# Light-Adapter_SMD.net
KiCad netlist of a schematic drawn in EAGLE
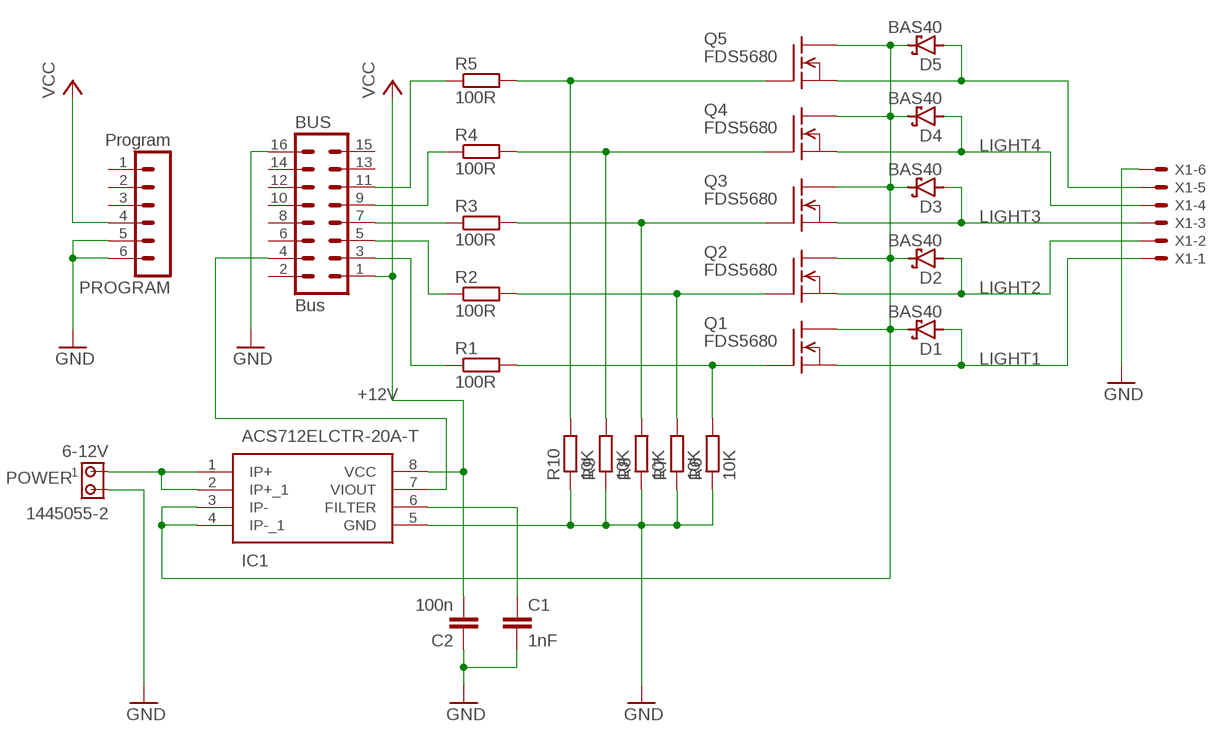
[diagram p0: schematic, sheet 1]

(export (version "E")
  (design (tool "Eeschema 10.0.6"))
  (components
    (comp (ref "6-12V")
      (value "1445055-2")
      (footprint "eagle-import:1445055-2")
      (libsource (lib "eagle-import") (part "1445055-2"))
    )
    (comp (ref "BUS")
      (value "Bus")
      (footprint "eagle-import:MA08-2")
      (libsource (lib "eagle-import") (part "MA08-2"))
    )
    (comp (ref "C1")
      (value "1nF")
      (footprint "eagle-import:C0402")
      (libsource (lib "eagle-import") (part "C-EUC0402"))
    )
    (comp (ref "C2")
      (value "100n")
      (footprint "eagle-import:C0402")
      (libsource (lib "eagle-import") (part "C-EUC0402"))
    )
    (comp (ref "D1")
      (value "BAS40")
      (footprint "eagle-import:SOT23")
      (libsource (lib "eagle-import") (part "BAS40"))
    )
    (comp (ref "D2")
      (value "BAS40")
      (footprint "eagle-import:SOT23")
      (libsource (lib "eagle-import") (part "BAS40"))
    )
    (comp (ref "D3")
      (value "BAS40")
      (footprint "eagle-import:SOT23")
      (libsource (lib "eagle-import") (part "BAS40"))
    )
    (comp (ref "D4")
      (value "BAS40")
      (footprint "eagle-import:SOT23")
      (libsource (lib "eagle-import") (part "BAS40"))
    )
    (comp (ref "D5")
      (value "BAS40")
      (footprint "eagle-import:SOT23")
      (libsource (lib "eagle-import") (part "BAS40"))
    )
    (comp (ref "IC1")
      (value "ACS712ELCTR-20A-T")
      (footprint "eagle-import:SOIC127P600X175-8N")
      (fields (field (name "RS_PART_NUMBER") "6807135P"))
      (libsource (lib "eagle-import") (part "ACS712ELCTR-20A-T"))
    )
    (comp (ref "PROGRAM")
      (value "Program")
      (footprint "eagle-import:MA06-1")
      (libsource (lib "eagle-import") (part "MA06-1"))
    )
    (comp (ref "Q1")
      (value "FDS5680")
      (footprint "eagle-import:SO-8")
      (libsource (lib "eagle-import") (part "FDS5680"))
    )
    (comp (ref "Q2")
      (value "FDS5680")
      (footprint "eagle-import:SO-8")
      (libsource (lib "eagle-import") (part "FDS5680"))
    )
    (comp (ref "Q3")
      (value "FDS5680")
      (footprint "eagle-import:SO-8")
      (libsource (lib "eagle-import") (part "FDS5680"))
    )
    (comp (ref "Q4")
      (value "FDS5680")
      (footprint "eagle-import:SO-8")
      (libsource (lib "eagle-import") (part "FDS5680"))
    )
    (comp (ref "Q5")
      (value "FDS5680")
      (footprint "eagle-import:SO-8")
      (libsource (lib "eagle-import") (part "FDS5680"))
    )
    (comp (ref "R1")
      (value "100R")
      (footprint "eagle-import:R0402")
      (libsource (lib "eagle-import") (part "R-EU_R0402"))
    )
    (comp (ref "R2")
      (value "100R")
      (footprint "eagle-import:R0402")
      (libsource (lib "eagle-import") (part "R-EU_R0402"))
    )
    (comp (ref "R3")
      (value "100R")
      (footprint "eagle-import:R0402")
      (libsource (lib "eagle-import") (part "R-EU_R0402"))
    )
    (comp (ref "R4")
      (value "100R")
      (footprint "eagle-import:R0402")
      (libsource (lib "eagle-import") (part "R-EU_R0402"))
    )
    (comp (ref "R5")
      (value "100R")
      (footprint "eagle-import:R0402")
      (libsource (lib "eagle-import") (part "R-EU_R0402"))
    )
    (comp (ref "R6")
      (value "10K")
      (footprint "eagle-import:R0402")
      (libsource (lib "eagle-import") (part "R-EU_R0402"))
    )
    (comp (ref "R7")
      (value "10K")
      (footprint "eagle-import:R0402")
      (libsource (lib "eagle-import") (part "R-EU_R0402"))
    )
    (comp (ref "R8")
      (value "10K")
      (footprint "eagle-import:R0402")
      (libsource (lib "eagle-import") (part "R-EU_R0402"))
    )
    (comp (ref "R9")
      (value "10K")
      (footprint "eagle-import:R0402")
      (libsource (lib "eagle-import") (part "R-EU_R0402"))
    )
    (comp (ref "R10")
      (value "10K")
      (footprint "eagle-import:R0402")
      (libsource (lib "eagle-import") (part "R-EU_R0402"))
    )
    (comp (ref "X1")
      (value "22-23-2061")
      (footprint "eagle-import:22-23-2061")
      (fields (field (name "MF") "MOLEX"))
      (libsource (lib "eagle-import") (part "22-23-2061"))
    )
  )
  (nets
    (net (code "1") (name "/+12V") (class "Default")
      (node (ref "D1") (pin "3") (pinfunction "C_3") (pintype "passive"))
      (node (ref "D2") (pin "3") (pinfunction "C_3") (pintype "passive"))
      (node (ref "D3") (pin "3") (pinfunction "C_3") (pintype "passive"))
      (node (ref "D4") (pin "3") (pinfunction "C_3") (pintype "passive"))
      (node (ref "D5") (pin "3") (pinfunction "C_3") (pintype "passive"))
      (node (ref "IC1") (pin "3") (pinfunction "IP-_3") (pintype "bidirectional"))
      (node (ref "IC1") (pin "4") (pinfunction "IP-_1_4") (pintype "bidirectional"))
      (node (ref "Q1") (pin "5") (pinfunction "D_5") (pintype "passive"))
      (node (ref "Q1") (pin "6") (pinfunction "D_6") (pintype "passive"))
      (node (ref "Q1") (pin "7") (pinfunction "D_7") (pintype "passive"))
      (node (ref "Q1") (pin "8") (pinfunction "D_8") (pintype "passive"))
      (node (ref "Q2") (pin "5") (pinfunction "D_5") (pintype "passive"))
      (node (ref "Q2") (pin "6") (pinfunction "D_6") (pintype "passive"))
      (node (ref "Q2") (pin "7") (pinfunction "D_7") (pintype "passive"))
      (node (ref "Q2") (pin "8") (pinfunction "D_8") (pintype "passive"))
      (node (ref "Q3") (pin "5") (pinfunction "D_5") (pintype "passive"))
      (node (ref "Q3") (pin "6") (pinfunction "D_6") (pintype "passive"))
      (node (ref "Q3") (pin "7") (pinfunction "D_7") (pintype "passive"))
      (node (ref "Q3") (pin "8") (pinfunction "D_8") (pintype "passive"))
      (node (ref "Q4") (pin "5") (pinfunction "D_5") (pintype "passive"))
      (node (ref "Q4") (pin "6") (pinfunction "D_6") (pintype "passive"))
      (node (ref "Q4") (pin "7") (pinfunction "D_7") (pintype "passive"))
      (node (ref "Q4") (pin "8") (pinfunction "D_8") (pintype "passive"))
      (node (ref "Q5") (pin "5") (pinfunction "D_5") (pintype "passive"))
      (node (ref "Q5") (pin "6") (pinfunction "D_6") (pintype "passive"))
      (node (ref "Q5") (pin "7") (pinfunction "D_7") (pintype "passive"))
      (node (ref "Q5") (pin "8") (pinfunction "D_8") (pintype "passive"))
    )
    (net (code "2") (name "/LIGHT1") (class "Default")
      (node (ref "D1") (pin "1") (pinfunction "A_1") (pintype "passive"))
      (node (ref "Q1") (pin "1") (pinfunction "S_1") (pintype "passive"))
      (node (ref "Q1") (pin "2") (pinfunction "S_2") (pintype "passive"))
      (node (ref "Q1") (pin "3") (pinfunction "S_3") (pintype "passive"))
      (node (ref "X1") (pin "1") (pinfunction "S_1") (pintype "passive"))
    )
    (net (code "3") (name "/LIGHT2") (class "Default")
      (node (ref "D2") (pin "1") (pinfunction "A_1") (pintype "passive"))
      (node (ref "Q2") (pin "1") (pinfunction "S_1") (pintype "passive"))
      (node (ref "Q2") (pin "2") (pinfunction "S_2") (pintype "passive"))
      (node (ref "Q2") (pin "3") (pinfunction "S_3") (pintype "passive"))
      (node (ref "X1") (pin "2") (pinfunction "S_2") (pintype "passive"))
    )
    (net (code "4") (name "/LIGHT3") (class "Default")
      (node (ref "D3") (pin "1") (pinfunction "A_1") (pintype "passive"))
      (node (ref "Q3") (pin "1") (pinfunction "S_1") (pintype "passive"))
      (node (ref "Q3") (pin "2") (pinfunction "S_2") (pintype "passive"))
      (node (ref "Q3") (pin "3") (pinfunction "S_3") (pintype "passive"))
      (node (ref "X1") (pin "3") (pinfunction "S_3") (pintype "passive"))
    )
    (net (code "5") (name "/LIGHT4") (class "Default")
      (node (ref "D4") (pin "1") (pinfunction "A_1") (pintype "passive"))
      (node (ref "Q4") (pin "1") (pinfunction "S_1") (pintype "passive"))
      (node (ref "Q4") (pin "2") (pinfunction "S_2") (pintype "passive"))
      (node (ref "Q4") (pin "3") (pinfunction "S_3") (pintype "passive"))
      (node (ref "X1") (pin "4") (pinfunction "S_4") (pintype "passive"))
    )
    (net (code "6") (name "/POWER") (class "Default")
      (node (ref "6-12V") (pin "1") (pinfunction "1_1") (pintype "passive"))
      (node (ref "IC1") (pin "1") (pinfunction "IP+_1") (pintype "bidirectional"))
      (node (ref "IC1") (pin "2") (pinfunction "IP+_1_2") (pintype "bidirectional"))
    )
    (net (code "7") (name "GND") (class "Default")
      (node (ref "6-12V") (pin "2") (pinfunction "2_2") (pintype "passive"))
      (node (ref "BUS") (pin "16") (pinfunction "16_16") (pintype "passive"))
      (node (ref "C1") (pin "2") (pinfunction "2_2") (pintype "passive"))
      (node (ref "C2") (pin "1") (pinfunction "1_1") (pintype "passive"))
      (node (ref "IC1") (pin "5") (pinfunction "GND_5") (pintype "power_in"))
      (node (ref "PROGRAM") (pin "5") (pinfunction "5_5") (pintype "passive"))
      (node (ref "PROGRAM") (pin "6") (pinfunction "6_6") (pintype "passive"))
      (node (ref "R10") (pin "1") (pinfunction "1_1") (pintype "passive"))
      (node (ref "R6") (pin "1") (pinfunction "1_1") (pintype "passive"))
      (node (ref "R7") (pin "1") (pinfunction "1_1") (pintype "passive"))
      (node (ref "R8") (pin "1") (pinfunction "1_1") (pintype "passive"))
      (node (ref "R9") (pin "1") (pinfunction "1_1") (pintype "passive"))
      (node (ref "X1") (pin "6") (pinfunction "S_6") (pintype "passive"))
    )
    (net (code "8") (name "Net-(BUS-Pad3)") (class "Default")
      (node (ref "BUS") (pin "3") (pinfunction "3_3") (pintype "passive"))
      (node (ref "R1") (pin "1") (pinfunction "1_1") (pintype "passive"))
    )
    (net (code "9") (name "Net-(BUS-Pad5)") (class "Default")
      (node (ref "BUS") (pin "5") (pinfunction "5_5") (pintype "passive"))
      (node (ref "R2") (pin "1") (pinfunction "1_1") (pintype "passive"))
    )
    (net (code "10") (name "Net-(BUS-Pad7)") (class "Default")
      (node (ref "BUS") (pin "7") (pinfunction "7_7") (pintype "passive"))
      (node (ref "R3") (pin "1") (pinfunction "1_1") (pintype "passive"))
    )
    (net (code "11") (name "Net-(BUS-Pad9)") (class "Default")
      (node (ref "BUS") (pin "9") (pinfunction "9_9") (pintype "passive"))
      (node (ref "R4") (pin "1") (pinfunction "1_1") (pintype "passive"))
    )
    (net (code "12") (name "Net-(BUS-Pad11)") (class "Default")
      (node (ref "BUS") (pin "11") (pinfunction "11_11") (pintype "passive"))
      (node (ref "R5") (pin "1") (pinfunction "1_1") (pintype "passive"))
    )
    (net (code "13") (name "Net-(D5-A)") (class "Default")
      (node (ref "D5") (pin "1") (pinfunction "A_1") (pintype "passive"))
      (node (ref "Q5") (pin "1") (pinfunction "S_1") (pintype "passive"))
      (node (ref "Q5") (pin "2") (pinfunction "S_2") (pintype "passive"))
      (node (ref "Q5") (pin "3") (pinfunction "S_3") (pintype "passive"))
      (node (ref "X1") (pin "5") (pinfunction "S_5") (pintype "passive"))
    )
    (net (code "14") (name "Net-(IC1-FILTER)") (class "Default")
      (node (ref "C1") (pin "1") (pinfunction "1_1") (pintype "passive"))
      (node (ref "IC1") (pin "6") (pinfunction "FILTER_6") (pintype "bidirectional"))
    )
    (net (code "15") (name "Net-(IC1-VIOUT)") (class "Default")
      (node (ref "BUS") (pin "4") (pinfunction "4_4") (pintype "passive"))
      (node (ref "IC1") (pin "7") (pinfunction "VIOUT_7") (pintype "bidirectional"))
    )
    (net (code "16") (name "Net-(Q1-G)") (class "Default")
      (node (ref "Q1") (pin "4") (pinfunction "G_4") (pintype "passive"))
      (node (ref "R1") (pin "2") (pinfunction "2_2") (pintype "passive"))
      (node (ref "R6") (pin "2") (pinfunction "2_2") (pintype "passive"))
    )
    (net (code "17") (name "Net-(Q2-G)") (class "Default")
      (node (ref "Q2") (pin "4") (pinfunction "G_4") (pintype "passive"))
      (node (ref "R2") (pin "2") (pinfunction "2_2") (pintype "passive"))
      (node (ref "R7") (pin "2") (pinfunction "2_2") (pintype "passive"))
    )
    (net (code "18") (name "Net-(Q3-G)") (class "Default")
      (node (ref "Q3") (pin "4") (pinfunction "G_4") (pintype "passive"))
      (node (ref "R3") (pin "2") (pinfunction "2_2") (pintype "passive"))
      (node (ref "R8") (pin "2") (pinfunction "2_2") (pintype "passive"))
    )
    (net (code "19") (name "Net-(Q4-G)") (class "Default")
      (node (ref "Q4") (pin "4") (pinfunction "G_4") (pintype "passive"))
      (node (ref "R4") (pin "2") (pinfunction "2_2") (pintype "passive"))
      (node (ref "R9") (pin "2") (pinfunction "2_2") (pintype "passive"))
    )
    (net (code "20") (name "Net-(Q5-G)") (class "Default")
      (node (ref "Q5") (pin "4") (pinfunction "G_4") (pintype "passive"))
      (node (ref "R10") (pin "2") (pinfunction "2_2") (pintype "passive"))
      (node (ref "R5") (pin "2") (pinfunction "2_2") (pintype "passive"))
    )
    (net (code "21") (name "VCC") (class "Default")
      (node (ref "BUS") (pin "1") (pinfunction "1_1") (pintype "passive"))
      (node (ref "C2") (pin "2") (pinfunction "2_2") (pintype "passive"))
      (node (ref "IC1") (pin "8") (pinfunction "VCC_8") (pintype "power_in"))
      (node (ref "PROGRAM") (pin "4") (pinfunction "4_4") (pintype "passive"))
    )
    (net (code "22") (name "unconnected-(BUS-Pad2)") (class "Default")
      (node (ref "BUS") (pin "2") (pinfunction "2_2") (pintype "passive"))
    )
    (net (code "23") (name "unconnected-(BUS-Pad6)") (class "Default")
      (node (ref "BUS") (pin "6") (pinfunction "6_6") (pintype "passive"))
    )
    (net (code "24") (name "unconnected-(BUS-Pad8)") (class "Default")
      (node (ref "BUS") (pin "8") (pinfunction "8_8") (pintype "passive"))
    )
    (net (code "25") (name "unconnected-(BUS-Pad10)") (class "Default")
      (node (ref "BUS") (pin "10") (pinfunction "10_10") (pintype "passive"))
    )
    (net (code "26") (name "unconnected-(BUS-Pad12)") (class "Default")
      (node (ref "BUS") (pin "12") (pinfunction "12_12") (pintype "passive"))
    )
    (net (code "27") (name "unconnected-(BUS-Pad13)") (class "Default")
      (node (ref "BUS") (pin "13") (pinfunction "13_13") (pintype "passive"))
    )
    (net (code "28") (name "unconnected-(BUS-Pad14)") (class "Default")
      (node (ref "BUS") (pin "14") (pinfunction "14_14") (pintype "passive"))
    )
    (net (code "29") (name "unconnected-(BUS-Pad15)") (class "Default")
      (node (ref "BUS") (pin "15") (pinfunction "15_15") (pintype "passive"))
    )
    (net (code "30") (name "unconnected-(PROGRAM-Pad1)") (class "Default")
      (node (ref "PROGRAM") (pin "1") (pinfunction "1_1") (pintype "passive"))
    )
    (net (code "31") (name "unconnected-(PROGRAM-Pad2)") (class "Default")
      (node (ref "PROGRAM") (pin "2") (pinfunction "2_2") (pintype "passive"))
    )
    (net (code "32") (name "unconnected-(PROGRAM-Pad3)") (class "Default")
      (node (ref "PROGRAM") (pin "3") (pinfunction "3_3") (pintype "passive"))
    )
  )
)
